# YOTSUBA_-Y-Z_ver_1_4.net
KiCad netlist of a schematic drawn in EAGLE
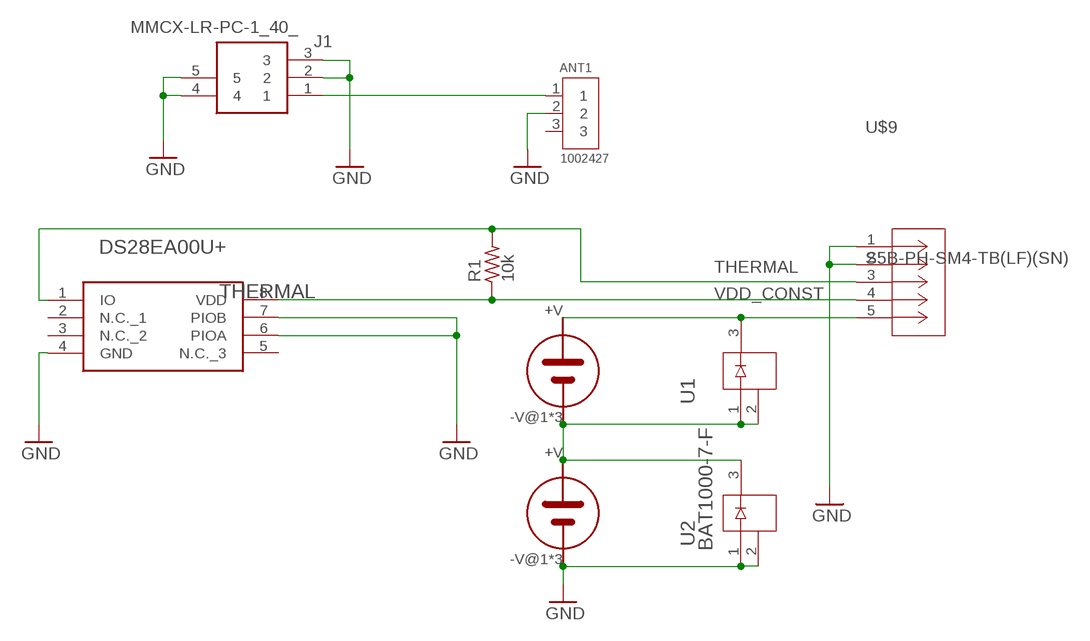
[diagram p0: schematic, sheet 1]

(export (version "E")
  (design (tool "Eeschema 10.0.6"))
  (components
    (comp (ref "ANT1")
      (value "1002427")
      (footprint "eagle-import:ANTENNA_1002427")
      (fields (field (name "DIGI-KEY_PART_NUMBER") "478-1002427TR-ND") (field (name "MF") "Ethertronics/AVX"))
      (libsource (lib "eagle-import") (part "1002427"))
    )
    (comp (ref "J1")
      (value "MMCX-LR-PC-1_40_")
      (footprint "eagle-import:MMCXLRPC140")
      (fields
        (field (name "MANUFACTURER_PART_NUMBER") "MMCX-LR-PC-1(40)")
        (field (name "MOUSER_PART_NUMBER") "798-MMCX-LR-PC-1(40)")
      )
      (libsource (lib "eagle-import") (part "MMCX-LR-PC-1_40_"))
    )
    (comp (ref "R1")
      (value "10k")
      (footprint "eagle-import:R0805")
      (libsource (lib "eagle-import") (part "R-US_R0805"))
    )
    (comp (ref "THERMAL")
      (value "DS28EA00U+")
      (footprint "eagle-import:SOP65P490X110-8N")
      (fields (field (name "MOUSER_PART_NUMBER") "700-DS28EA00U"))
      (libsource (lib "eagle-import") (part "DS28EA00U+"))
    )
    (comp (ref "U$2")
      (value "3G30A")
      (footprint "eagle-import:SOLAR_3G30A")
      (libsource (lib "eagle-import") (part "3G30A"))
    )
    (comp (ref "U$3")
      (value "3G30A")
      (footprint "eagle-import:SOLAR_3G30A")
      (libsource (lib "eagle-import") (part "3G30A"))
    )
    (comp (ref "U$9")
      (value "S5B-PH-SM4-TB(LF)(SN)")
      (footprint "eagle-import:CONN_S5B-PH-SM4-TB_JST")
      (fields (field (name "COPYRIGHT") "Copyright (C) 2023 Ultra Librarian. All rights reserved."))
      (libsource (lib "eagle-import") (part "S5B-PH-SM4-TB(LF)(SN)"))
    )
    (comp (ref "U1")
      (value "BAT1000-7-F")
      (footprint "eagle-import:SOT23_BAT_DIO")
      (fields (field (name "COPYRIGHT") "Copyright (C) 2023 Ultra Librarian. All rights reserved."))
      (libsource (lib "eagle-import") (part "BAT1000-7-F"))
    )
    (comp (ref "U2")
      (value "BAT1000-7-F")
      (footprint "eagle-import:SOT23_BAT_DIO")
      (fields (field (name "COPYRIGHT") "Copyright (C) 2023 Ultra Librarian. All rights reserved."))
      (libsource (lib "eagle-import") (part "BAT1000-7-F"))
    )
  )
  (nets
    (net (code "1") (name "/THERMAL") (class "Default")
      (node (ref "R1") (pin "2") (pinfunction "2_2") (pintype "passive"))
      (node (ref "THERMAL") (pin "1") (pinfunction "IO_1") (pintype "bidirectional"))
      (node (ref "U$9") (pin "3") (pinfunction "3_3") (pintype "passive"))
    )
    (net (code "2") (name "/VDD_CONST") (class "Default")
      (node (ref "R1") (pin "1") (pinfunction "1_1") (pintype "passive"))
      (node (ref "THERMAL") (pin "8") (pinfunction "VDD_8") (pintype "bidirectional"))
      (node (ref "U$9") (pin "4") (pinfunction "4_4") (pintype "passive"))
    )
    (net (code "3") (name "GND") (class "Default")
      (node (ref "ANT1") (pin "2") (pinfunction "2_2") (pintype "passive"))
      (node (ref "J1") (pin "2") (pinfunction "2_2") (pintype "bidirectional"))
      (node (ref "J1") (pin "3") (pinfunction "3_3") (pintype "bidirectional"))
      (node (ref "J1") (pin "4") (pinfunction "4_4") (pintype "bidirectional"))
      (node (ref "J1") (pin "5") (pinfunction "5_5") (pintype "bidirectional"))
      (node (ref "THERMAL") (pin "4") (pinfunction "GND_4") (pintype "bidirectional"))
      (node (ref "THERMAL") (pin "6") (pinfunction "PIOA_6") (pintype "bidirectional"))
      (node (ref "THERMAL") (pin "7") (pinfunction "PIOB_7") (pintype "bidirectional"))
      (node (ref "U$3") (pin "-V@1") (pinfunction "-V_-V@1") (pintype "bidirectional"))
      (node (ref "U$3") (pin "-V@2") (pinfunction "-V_-V@2") (pintype "bidirectional"))
      (node (ref "U$3") (pin "-V@3") (pinfunction "-V_-V@3") (pintype "bidirectional"))
      (node (ref "U$9") (pin "1") (pinfunction "1_1") (pintype "passive"))
      (node (ref "U$9") (pin "2") (pinfunction "2_2") (pintype "passive"))
      (node (ref "U2") (pin "1") (pinfunction "1_1") (pintype "passive"))
      (node (ref "U2") (pin "2") (pinfunction "2_2") (pintype "passive"))
    )
    (net (code "4") (name "Net-(ANT1-Pad1)") (class "Default")
      (node (ref "ANT1") (pin "1") (pinfunction "1_1") (pintype "passive"))
      (node (ref "J1") (pin "1") (pinfunction "1_1") (pintype "bidirectional"))
    )
    (net (code "5") (name "Net-(U$2--V-Pad-V@1)") (class "Default")
      (node (ref "U$2") (pin "-V@1") (pinfunction "-V_-V@1") (pintype "bidirectional"))
      (node (ref "U$2") (pin "-V@2") (pinfunction "-V_-V@2") (pintype "bidirectional"))
      (node (ref "U$2") (pin "-V@3") (pinfunction "-V_-V@3") (pintype "bidirectional"))
      (node (ref "U$3") (pin "+V") (pinfunction "+V_+V") (pintype "bidirectional"))
      (node (ref "U1") (pin "1") (pinfunction "1_1") (pintype "passive"))
      (node (ref "U1") (pin "2") (pinfunction "2_2") (pintype "passive"))
      (node (ref "U2") (pin "3") (pinfunction "3_3") (pintype "passive"))
    )
    (net (code "6") (name "Net-(U$2-Pad+V)") (class "Default")
      (node (ref "U$2") (pin "+V") (pinfunction "+V_+V") (pintype "bidirectional"))
      (node (ref "U$9") (pin "5") (pinfunction "5_5") (pintype "passive"))
      (node (ref "U1") (pin "3") (pinfunction "3_3") (pintype "passive"))
    )
    (net (code "7") (name "unconnected-(ANT1-Pad3)") (class "Default")
      (node (ref "ANT1") (pin "3") (pinfunction "3_3") (pintype "passive"))
    )
    (net (code "8") (name "unconnected-(THERMAL-N.C._1-Pad2)") (class "Default")
      (node (ref "THERMAL") (pin "2") (pinfunction "N.C._1_2") (pintype "bidirectional"))
    )
    (net (code "9") (name "unconnected-(THERMAL-N.C._2-Pad3)") (class "Default")
      (node (ref "THERMAL") (pin "3") (pinfunction "N.C._2_3") (pintype "bidirectional"))
    )
    (net (code "10") (name "unconnected-(THERMAL-N.C._3-Pad5)") (class "Default")
      (node (ref "THERMAL") (pin "5") (pinfunction "N.C._3_5") (pintype "bidirectional"))
    )
  )
)
